# XM-06_Typical_Application_Circuit.net
KiCad netlist of a schematic drawn in Altium Designer
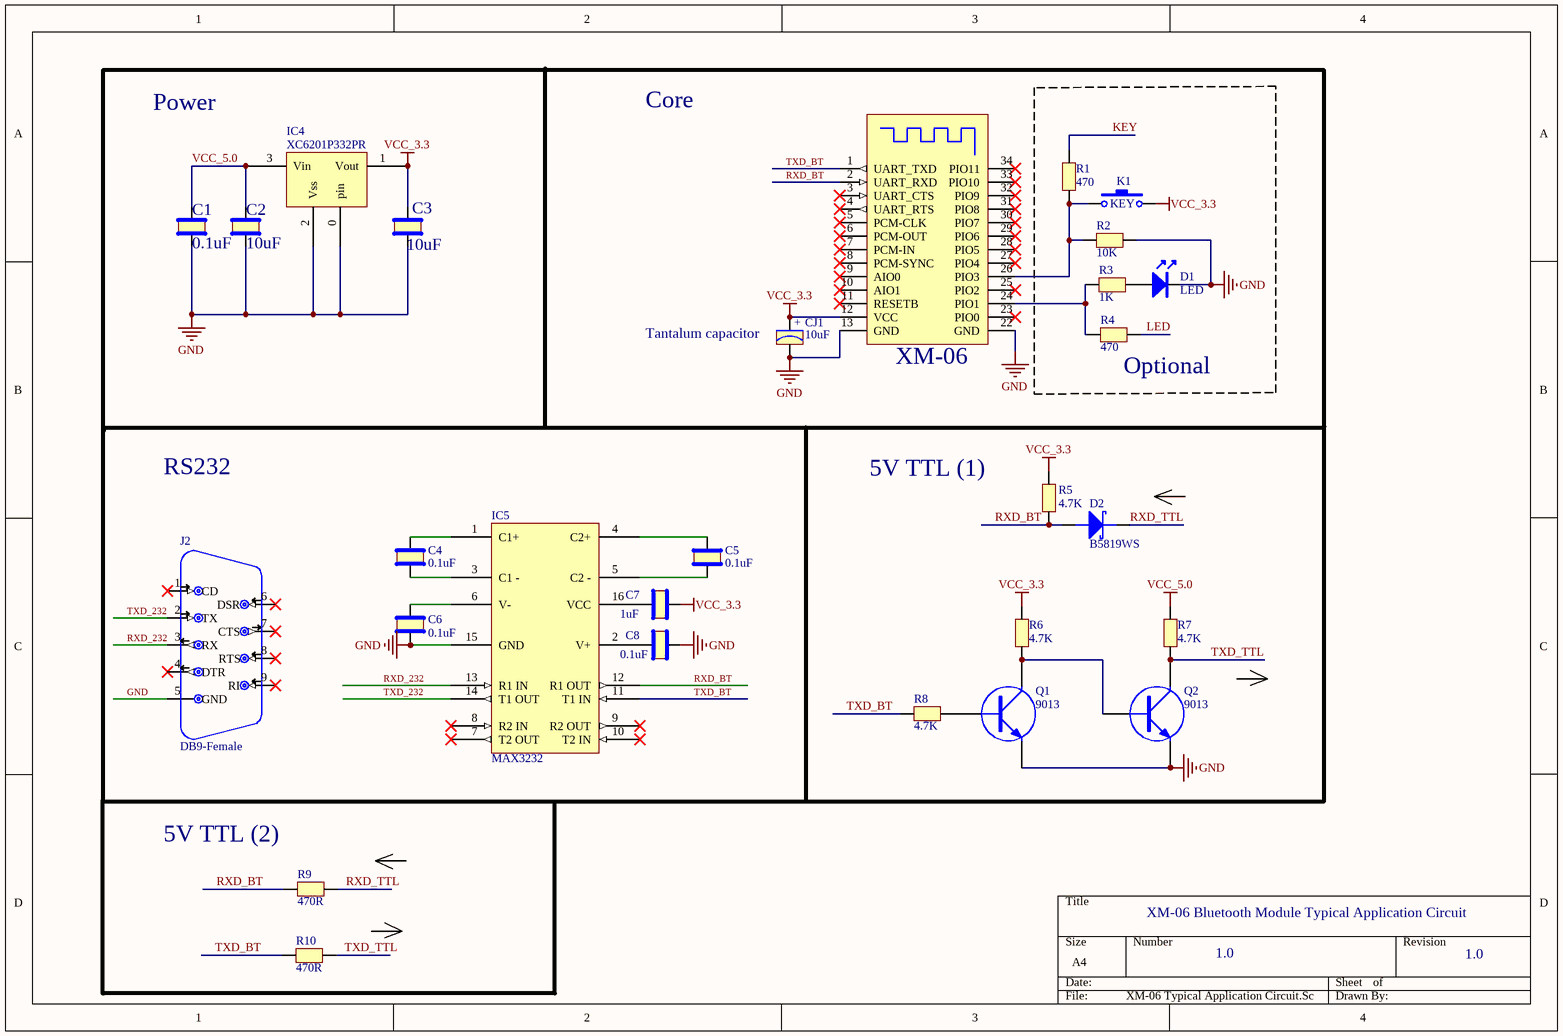
[diagram p0: XM-06 Typical Application Circuit.SchDoc]

(export (version "E")
  (design (tool "Eeschema 10.0.6"))
  (components
    (comp (ref "*1") (value "XM-06") (libsource (lib "wbh") (part "XM-101")))
    (comp (ref "C1") (value "0.1uF") (footprint "0603.RC") (libsource (lib "*") (part "CAP")))
    (comp (ref "C2") (value "10uF") (footprint "0603.RC") (libsource (lib "*") (part "CAP")))
    (comp (ref "C3") (value "10uF") (footprint "0603.RC") (libsource (lib "*") (part "CAP")))
    (comp (ref "C4") (value "0.1uF") (footprint "0603.RC") (libsource (lib "*") (part "CAP")))
    (comp (ref "C5") (value "0.1uF") (footprint "0603.RC") (libsource (lib "") (part "CAP_1")))
    (comp (ref "C6") (value "0.1uF") (footprint "0603.RC") (libsource (lib "*") (part "CAP")))
    (comp (ref "C7") (value "1uF") (footprint "0603.RC") (libsource (lib "") (part "CAP_2")))
    (comp (ref "C8") (value "0.1uF") (footprint "0603.RC") (libsource (lib "") (part "CAP_2")))
    (comp (ref "CJ1") (value "10uF") (footprint "1206.DC") (libsource (lib "wbh") (part "CAPJS")))
    (comp (ref "D1") (value "LED") (footprint "0603+") (libsource (lib "*") (part "LED")))
    (comp (ref "D2")
      (value "B5819WS")
      (footprint "SOD-323 - SMT")
      (description "Schottky Diode")
      (libsource (lib "wbh") (part "DIODE SCHOTTKY"))
    )
    (comp (ref "IC4") (value "XC6201P332PR") (footprint "SOT-89") (libsource (lib "*") (part "XC6201P301PR")))
    (comp (ref "IC5") (value "MAX3232") (footprint "SOP-16(N)") (libsource (lib "wbh") (part "MAX3232")))
    (comp (ref "J2") (value "DB9-Female") (footprint "DB9-F - 90") (libsource (lib "wbh") (part "DB9-F")))
    (comp (ref "K1") (value "KEY") (footprint "KEY-SS204") (libsource (lib "wbh") (part "SW-KEYSMT1")))
    (comp (ref "Q1")
      (value "9013")
      (footprint "SMT-SOT23MOS")
      (description "NPN Transistor")
      (libsource (lib "wbh") (part "NPN"))
    )
    (comp (ref "Q2")
      (value "9013")
      (footprint "SMT-SOT23MOS")
      (description "NPN Transistor")
      (libsource (lib "wbh") (part "NPN"))
    )
    (comp (ref "R1") (value "470") (footprint "0603.RC") (libsource (lib "wbh") (part "RES")))
    (comp (ref "R2") (value "10K") (footprint "0603.RC") (libsource (lib "") (part "RES_1")))
    (comp (ref "R3") (value "1K") (footprint "0603.RC") (libsource (lib "") (part "RES_1")))
    (comp (ref "R4") (value "470") (footprint "0603.RC") (libsource (lib "") (part "RES_1")))
    (comp (ref "R5") (value "4.7K") (footprint "0603.RC") (libsource (lib "") (part "RES_2")))
    (comp (ref "R6") (value "4.7K") (footprint "0603.RC") (libsource (lib "") (part "RES_3")))
    (comp (ref "R7") (value "4.7K") (footprint "0603.RC") (libsource (lib "") (part "RES_3")))
    (comp (ref "R8") (value "4.7K") (footprint "0603.RC") (libsource (lib "wbh") (part "RES")))
    (comp (ref "R9") (value "470R") (footprint "0603.RC") (libsource (lib "wbh") (part "RES")))
    (comp (ref "R10") (value "470R") (footprint "0603.RC") (libsource (lib "wbh") (part "RES")))
  )
  (nets
    (net (code "1") (name "/KEY") (class "Default")
      (node (ref "R1") (pin "1") (pinfunction "1_1") (pintype "passive"))
    )
    (net (code "2") (name "/LED") (class "Default")
      (node (ref "R4") (pin "1") (pinfunction "1_1") (pintype "passive"))
    )
    (net (code "3") (name "/RXD_232") (class "Default")
      (node (ref "IC5") (pin "13") (pinfunction "R1_IN_13") (pintype "input"))
      (node (ref "J2") (pin "3") (pinfunction "RX_3") (pintype "output"))
    )
    (net (code "4") (name "/RXD_BT") (class "Default")
      (node (ref "*1") (pin "2") (pinfunction "UART_RXD_2") (pintype "input"))
      (node (ref "D2") (pin "1") (pinfunction "1_1") (pintype "passive"))
      (node (ref "IC5") (pin "12") (pinfunction "R1_OUT_12") (pintype "output"))
      (node (ref "R5") (pin "1") (pinfunction "1_1") (pintype "passive"))
      (node (ref "R9") (pin "2") (pinfunction "2_2") (pintype "passive"))
    )
    (net (code "5") (name "/RXD_TTL") (class "Default")
      (node (ref "D2") (pin "2") (pinfunction "2_2") (pintype "passive"))
      (node (ref "R9") (pin "1") (pinfunction "1_1") (pintype "passive"))
    )
    (net (code "6") (name "/TXD_232") (class "Default")
      (node (ref "IC5") (pin "14") (pinfunction "T1_OUT_14") (pintype "output"))
      (node (ref "J2") (pin "2") (pinfunction "TX_2") (pintype "input"))
    )
    (net (code "7") (name "/TXD_BT") (class "Default")
      (node (ref "*1") (pin "1") (pinfunction "UART_TXD_1") (pintype "output"))
      (node (ref "IC5") (pin "11") (pinfunction "T1_IN_11") (pintype "input"))
      (node (ref "R10") (pin "2") (pinfunction "2_2") (pintype "passive"))
      (node (ref "R8") (pin "2") (pinfunction "2_2") (pintype "passive"))
    )
    (net (code "8") (name "/TXD_TTL") (class "Default")
      (node (ref "Q2") (pin "D") (pinfunction "D_D") (pintype "passive"))
      (node (ref "R10") (pin "1") (pinfunction "1_1") (pintype "passive"))
      (node (ref "R7") (pin "1") (pinfunction "1_1") (pintype "passive"))
    )
    (net (code "9") (name "GND") (class "Default")
      (node (ref "*1") (pin "13") (pinfunction "GND_13") (pintype "passive"))
      (node (ref "*1") (pin "22") (pinfunction "GND_22") (pintype "passive"))
      (node (ref "C1") (pin "1") (pinfunction "1_1") (pintype "passive"))
      (node (ref "C2") (pin "1") (pinfunction "1_1") (pintype "passive"))
      (node (ref "C3") (pin "1") (pinfunction "1_1") (pintype "passive"))
      (node (ref "C6") (pin "1") (pinfunction "1_1") (pintype "passive"))
      (node (ref "C8") (pin "1") (pinfunction "1_1") (pintype "passive"))
      (node (ref "CJ1") (pin "K") (pinfunction "K_K") (pintype "passive"))
      (node (ref "D1") (pin "K") (pintype "passive"))
      (node (ref "IC4") (pin "0") (pinfunction "pin_0") (pintype "passive"))
      (node (ref "IC4") (pin "2") (pinfunction "Vss_2") (pintype "passive"))
      (node (ref "IC5") (pin "15") (pinfunction "GND_15") (pintype "power_in"))
      (node (ref "J2") (pin "5") (pinfunction "GND_5") (pintype "power_in"))
      (node (ref "Q1") (pin "S") (pinfunction "S_S") (pintype "passive"))
      (node (ref "Q2") (pin "S") (pinfunction "S_S") (pintype "passive"))
      (node (ref "R2") (pin "1") (pinfunction "1_1") (pintype "passive"))
    )
    (net (code "10") (name "Net-(*1-PIO1)") (class "Default")
      (node (ref "*1") (pin "24") (pinfunction "PIO1_24") (pintype "passive"))
      (node (ref "R3") (pin "2") (pinfunction "2_2") (pintype "passive"))
      (node (ref "R4") (pin "2") (pinfunction "2_2") (pintype "passive"))
    )
    (net (code "11") (name "Net-(*1-PIO3)") (class "Default")
      (node (ref "*1") (pin "26") (pinfunction "PIO3_26") (pintype "passive"))
      (node (ref "K1") (pin "2") (pinfunction "2_2") (pintype "passive"))
      (node (ref "R1") (pin "2") (pinfunction "2_2") (pintype "passive"))
      (node (ref "R2") (pin "2") (pinfunction "2_2") (pintype "passive"))
    )
    (net (code "12") (name "Net-(D1-PadA)") (class "Default")
      (node (ref "D1") (pin "A") (pintype "passive"))
      (node (ref "R3") (pin "1") (pinfunction "1_1") (pintype "passive"))
    )
    (net (code "13") (name "Net-(IC5-C1+)") (class "Default")
      (node (ref "C4") (pin "2") (pinfunction "2_2") (pintype "passive"))
      (node (ref "IC5") (pin "1") (pinfunction "C1+_1") (pintype "passive"))
    )
    (net (code "14") (name "Net-(IC5-C1_-)") (class "Default")
      (node (ref "C4") (pin "1") (pinfunction "1_1") (pintype "passive"))
      (node (ref "IC5") (pin "3") (pinfunction "C1_-_3") (pintype "passive"))
    )
    (net (code "15") (name "Net-(IC5-C2+)") (class "Default")
      (node (ref "C5") (pin "1") (pinfunction "1_1") (pintype "passive"))
      (node (ref "IC5") (pin "4") (pinfunction "C2+_4") (pintype "passive"))
    )
    (net (code "16") (name "Net-(IC5-C2_-)") (class "Default")
      (node (ref "C5") (pin "2") (pinfunction "2_2") (pintype "passive"))
      (node (ref "IC5") (pin "5") (pinfunction "C2_-_5") (pintype "passive"))
    )
    (net (code "17") (name "Net-(IC5-V+)") (class "Default")
      (node (ref "C8") (pin "2") (pinfunction "2_2") (pintype "passive"))
      (node (ref "IC5") (pin "2") (pinfunction "V+_2") (pintype "passive"))
    )
    (net (code "18") (name "Net-(IC5-V-)") (class "Default")
      (node (ref "C6") (pin "2") (pinfunction "2_2") (pintype "passive"))
      (node (ref "IC5") (pin "6") (pinfunction "V-_6") (pintype "power_in"))
    )
    (net (code "19") (name "Net-(IC5-VCC)") (class "Default")
      (node (ref "C7") (pin "2") (pinfunction "2_2") (pintype "passive"))
      (node (ref "IC5") (pin "16") (pinfunction "VCC_16") (pintype "power_in"))
    )
    (net (code "20") (name "Net-(Q1-PadD)") (class "Default")
      (node (ref "Q1") (pin "D") (pinfunction "D_D") (pintype "passive"))
      (node (ref "Q2") (pin "G") (pinfunction "G_G") (pintype "passive"))
      (node (ref "R6") (pin "1") (pinfunction "1_1") (pintype "passive"))
    )
    (net (code "21") (name "Net-(Q1-PadG)") (class "Default")
      (node (ref "Q1") (pin "G") (pinfunction "G_G") (pintype "passive"))
      (node (ref "R8") (pin "1") (pinfunction "1_1") (pintype "passive"))
    )
    (net (code "22") (name "VCC_3.3") (class "Default")
      (node (ref "*1") (pin "12") (pinfunction "VCC_12") (pintype "power_in"))
      (node (ref "C3") (pin "2") (pinfunction "2_2") (pintype "passive"))
      (node (ref "C7") (pin "1") (pinfunction "1_1") (pintype "passive"))
      (node (ref "CJ1") (pin "A") (pinfunction "A_A") (pintype "passive"))
      (node (ref "IC4") (pin "1") (pinfunction "Vout_1") (pintype "passive"))
      (node (ref "K1") (pin "1") (pinfunction "1_1") (pintype "passive"))
      (node (ref "R5") (pin "2") (pinfunction "2_2") (pintype "passive"))
      (node (ref "R6") (pin "2") (pinfunction "2_2") (pintype "passive"))
    )
    (net (code "23") (name "VCC_5.0") (class "Default")
      (node (ref "C1") (pin "2") (pinfunction "2_2") (pintype "passive"))
      (node (ref "C2") (pin "2") (pinfunction "2_2") (pintype "passive"))
      (node (ref "IC4") (pin "3") (pinfunction "Vin_3") (pintype "passive"))
      (node (ref "R7") (pin "2") (pinfunction "2_2") (pintype "passive"))
    )
    (net (code "24") (name "unconnected-(*1-AIO0-Pad9)") (class "Default")
      (node (ref "*1") (pin "9") (pinfunction "AIO0_9") (pintype "passive+no_connect"))
    )
    (net (code "25") (name "unconnected-(*1-AIO1-Pad10)") (class "Default")
      (node (ref "*1") (pin "10") (pinfunction "AIO1_10") (pintype "passive+no_connect"))
    )
    (net (code "26") (name "unconnected-(*1-PCM-CLK-Pad5)") (class "Default")
      (node (ref "*1") (pin "5") (pinfunction "PCM-CLK_5") (pintype "passive+no_connect"))
    )
    (net (code "27") (name "unconnected-(*1-PCM-IN-Pad7)") (class "Default")
      (node (ref "*1") (pin "7") (pinfunction "PCM-IN_7") (pintype "passive+no_connect"))
    )
    (net (code "28") (name "unconnected-(*1-PCM-OUT-Pad6)") (class "Default")
      (node (ref "*1") (pin "6") (pinfunction "PCM-OUT_6") (pintype "passive+no_connect"))
    )
    (net (code "29") (name "unconnected-(*1-PCM-SYNC-Pad8)") (class "Default")
      (node (ref "*1") (pin "8") (pinfunction "PCM-SYNC_8") (pintype "passive+no_connect"))
    )
    (net (code "30") (name "unconnected-(*1-PIO0-Pad23)") (class "Default")
      (node (ref "*1") (pin "23") (pinfunction "PIO0_23") (pintype "passive+no_connect"))
    )
    (net (code "31") (name "unconnected-(*1-PIO2-Pad25)") (class "Default")
      (node (ref "*1") (pin "25") (pinfunction "PIO2_25") (pintype "passive+no_connect"))
    )
    (net (code "32") (name "unconnected-(*1-PIO4-Pad27)") (class "Default")
      (node (ref "*1") (pin "27") (pinfunction "PIO4_27") (pintype "passive+no_connect"))
    )
    (net (code "33") (name "unconnected-(*1-PIO5-Pad28)") (class "Default")
      (node (ref "*1") (pin "28") (pinfunction "PIO5_28") (pintype "passive+no_connect"))
    )
    (net (code "34") (name "unconnected-(*1-PIO6-Pad29)") (class "Default")
      (node (ref "*1") (pin "29") (pinfunction "PIO6_29") (pintype "passive+no_connect"))
    )
    (net (code "35") (name "unconnected-(*1-PIO7-Pad30)") (class "Default")
      (node (ref "*1") (pin "30") (pinfunction "PIO7_30") (pintype "passive+no_connect"))
    )
    (net (code "36") (name "unconnected-(*1-PIO8-Pad31)") (class "Default")
      (node (ref "*1") (pin "31") (pinfunction "PIO8_31") (pintype "passive+no_connect"))
    )
    (net (code "37") (name "unconnected-(*1-PIO9-Pad32)") (class "Default")
      (node (ref "*1") (pin "32") (pinfunction "PIO9_32") (pintype "passive+no_connect"))
    )
    (net (code "38") (name "unconnected-(*1-PIO10-Pad33)") (class "Default")
      (node (ref "*1") (pin "33") (pinfunction "PIO10_33") (pintype "passive+no_connect"))
    )
    (net (code "39") (name "unconnected-(*1-PIO11-Pad34)") (class "Default")
      (node (ref "*1") (pin "34") (pinfunction "PIO11_34") (pintype "passive+no_connect"))
    )
    (net (code "40") (name "unconnected-(*1-RESETB-Pad11)") (class "Default")
      (node (ref "*1") (pin "11") (pinfunction "RESETB_11") (pintype "passive+no_connect"))
    )
    (net (code "41") (name "unconnected-(*1-UART_CTS-Pad3)") (class "Default")
      (node (ref "*1") (pin "3") (pinfunction "UART_CTS_3") (pintype "input+no_connect"))
    )
    (net (code "42") (name "unconnected-(*1-UART_RTS-Pad4)") (class "Default")
      (node (ref "*1") (pin "4") (pinfunction "UART_RTS_4") (pintype "output+no_connect"))
    )
    (net (code "43") (name "unconnected-(IC5-R2_IN-Pad8)") (class "Default")
      (node (ref "IC5") (pin "8") (pinfunction "R2_IN_8") (pintype "input+no_connect"))
    )
    (net (code "44") (name "unconnected-(IC5-R2_OUT-Pad9)") (class "Default")
      (node (ref "IC5") (pin "9") (pinfunction "R2_OUT_9") (pintype "output+no_connect"))
    )
    (net (code "45") (name "unconnected-(IC5-T2_IN-Pad10)") (class "Default")
      (node (ref "IC5") (pin "10") (pinfunction "T2_IN_10") (pintype "input+no_connect"))
    )
    (net (code "46") (name "unconnected-(IC5-T2_OUT-Pad7)") (class "Default")
      (node (ref "IC5") (pin "7") (pinfunction "T2_OUT_7") (pintype "output+no_connect"))
    )
    (net (code "47") (name "unconnected-(J2-CD-Pad1)") (class "Default")
      (node (ref "J2") (pin "1") (pinfunction "CD_1") (pintype "input+no_connect"))
    )
    (net (code "48") (name "unconnected-(J2-CTS-Pad7)") (class "Default")
      (node (ref "J2") (pin "7") (pinfunction "CTS_7") (pintype "output+no_connect"))
    )
    (net (code "49") (name "unconnected-(J2-DSR-Pad6)") (class "Default")
      (node (ref "J2") (pin "6") (pinfunction "DSR_6") (pintype "input+no_connect"))
    )
    (net (code "50") (name "unconnected-(J2-DTR-Pad4)") (class "Default")
      (node (ref "J2") (pin "4") (pinfunction "DTR_4") (pintype "output+no_connect"))
    )
    (net (code "51") (name "unconnected-(J2-RI-Pad9)") (class "Default")
      (node (ref "J2") (pin "9") (pinfunction "RI_9") (pintype "input+no_connect"))
    )
    (net (code "52") (name "unconnected-(J2-RTS-Pad8)") (class "Default")
      (node (ref "J2") (pin "8") (pinfunction "RTS_8") (pintype "input+no_connect"))
    )
  )
)
